# myg102.net
KiCad netlist of a schematic drawn in EasyEDA Pro
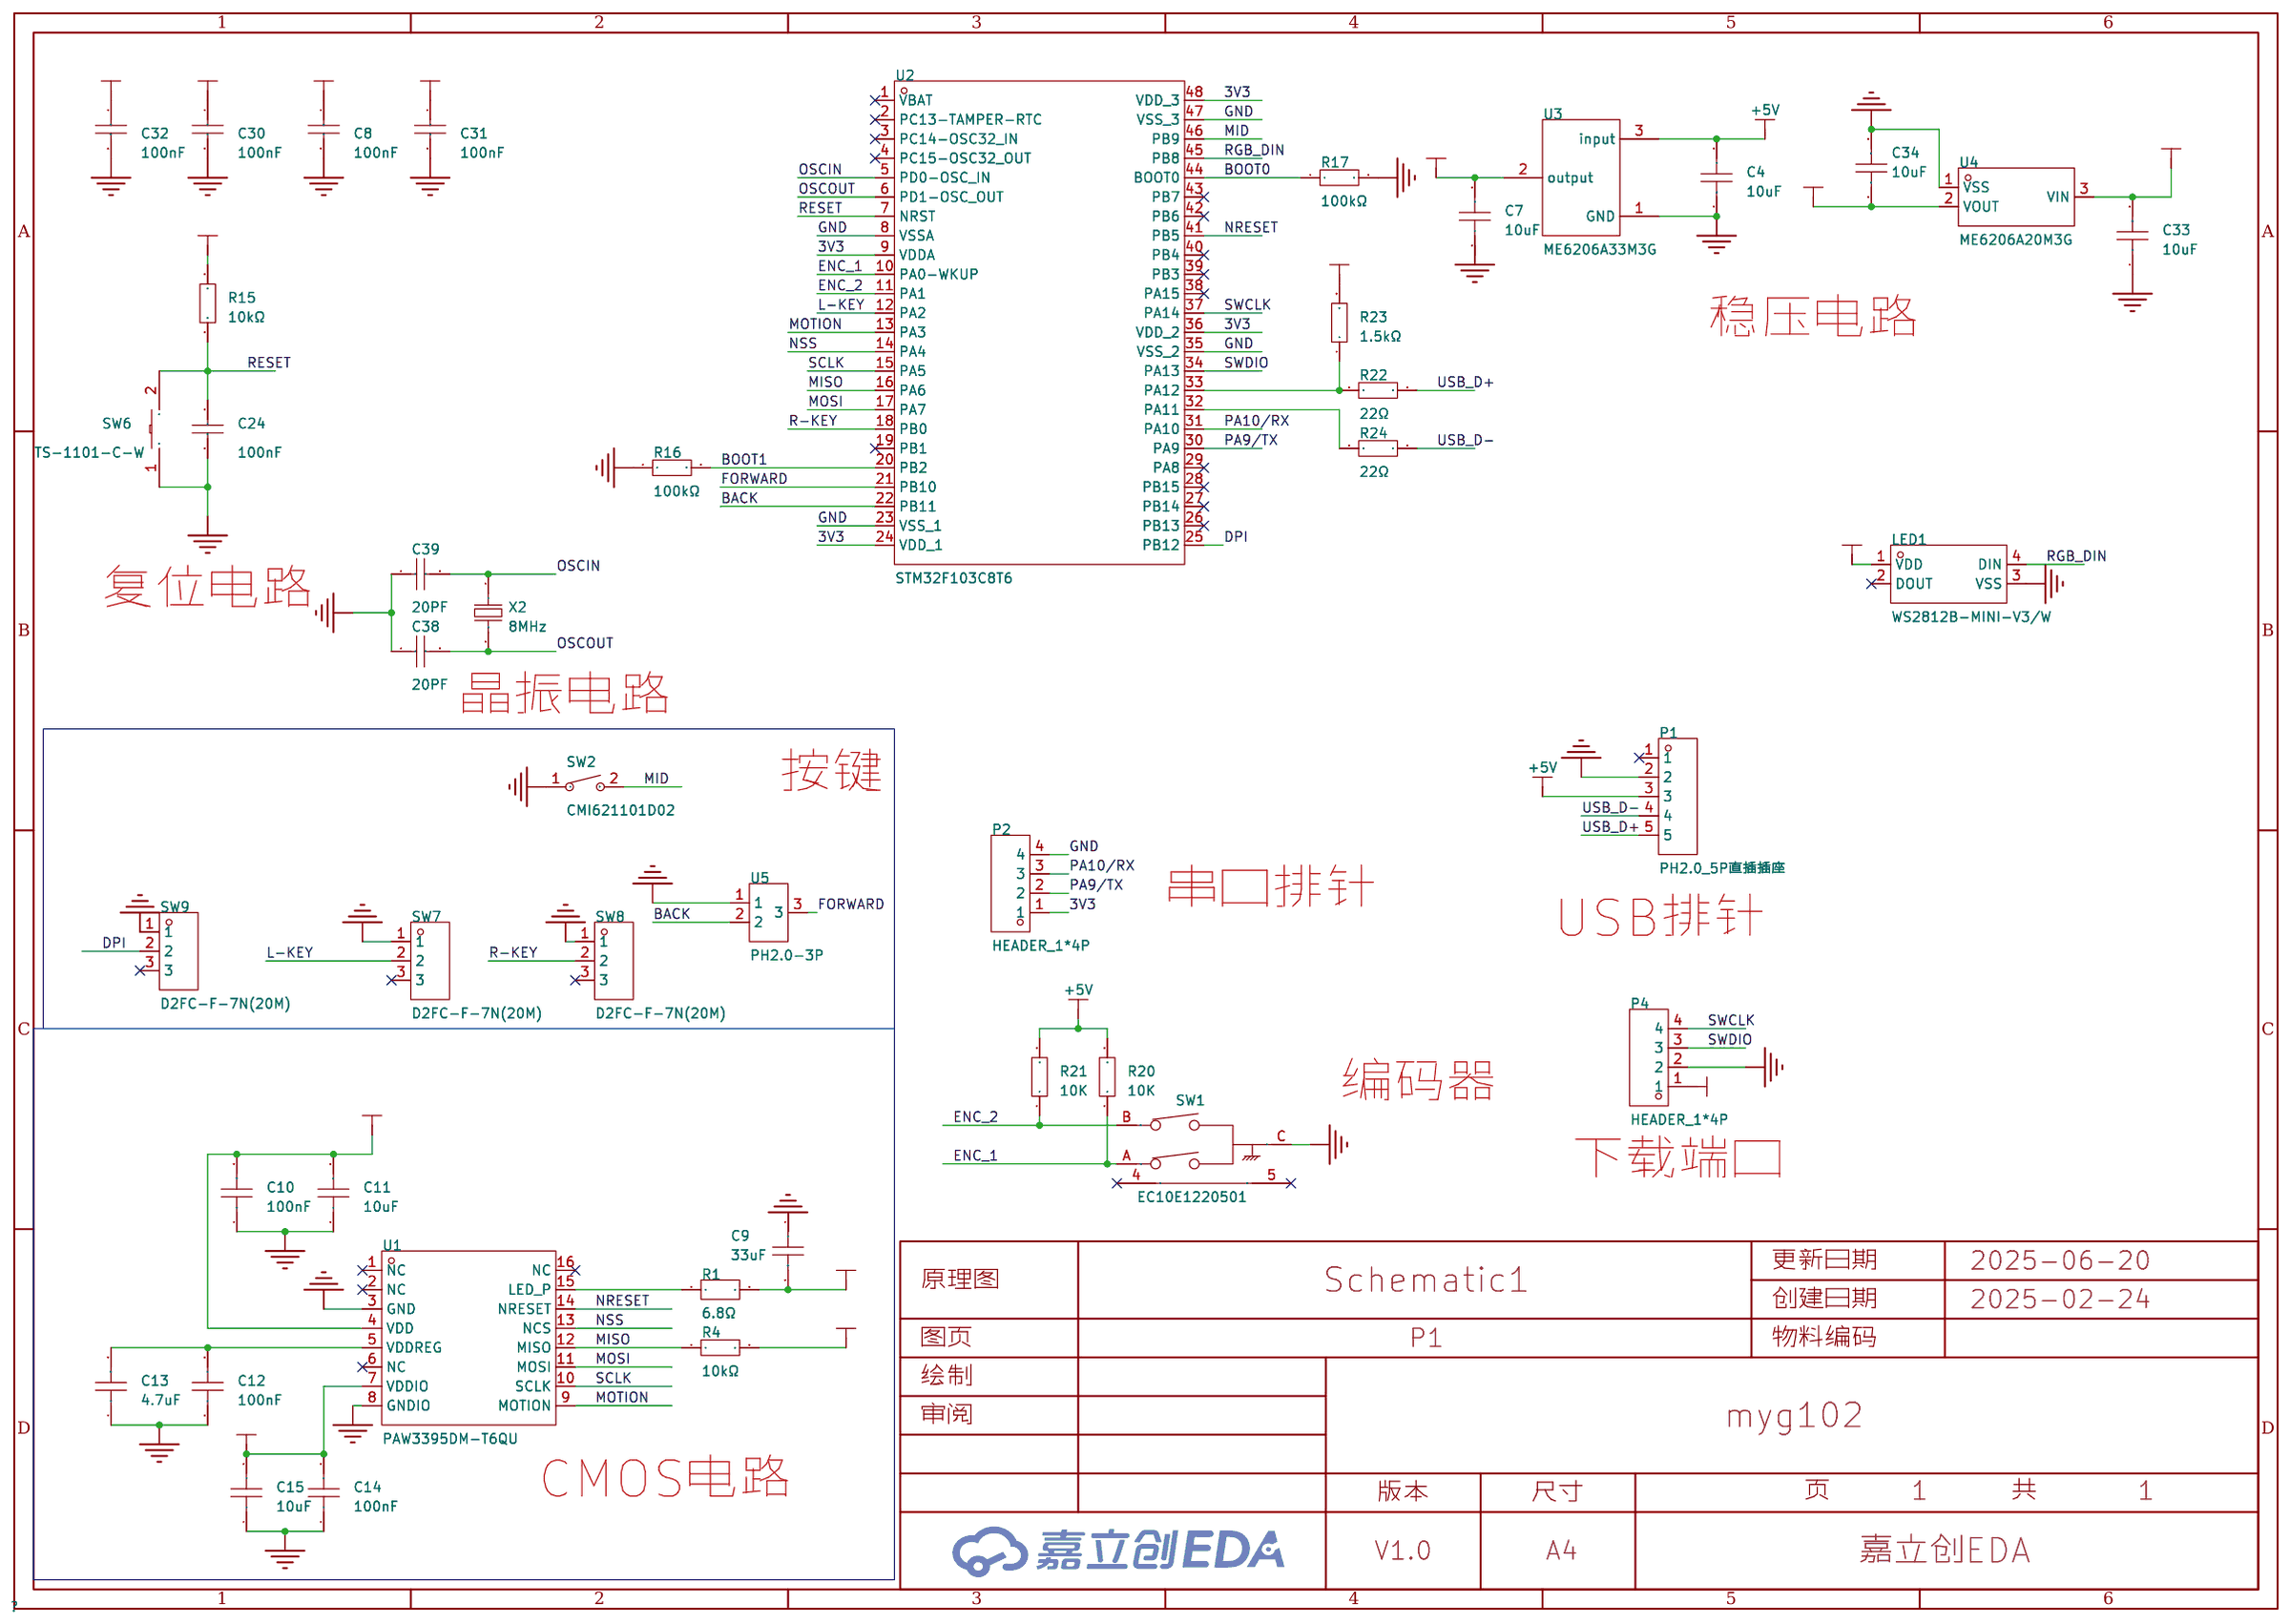
[diagram p0: schematic sheet]

(export (version "E")
  (design (tool "Eeschema 10.0.6"))
  (components
    (comp (ref "C4")
      (value "10uF")
      (footprint "easyedapro:C0603")
      (libsource (lib "easyedapro") (part "CapAcitance"))
    )
    (comp (ref "C7")
      (value "10uF")
      (footprint "easyedapro:C0603")
      (libsource (lib "easyedapro") (part "CapAcitance"))
    )
    (comp (ref "C8")
      (value "100nF")
      (footprint "easyedapro:C0603")
      (description "容值:100nF;精度:±10%;额定电压:50V;材质(温度系数):X7R;")
      (fields (field (name "Manufacturer Part") "0603B104K500NT") (field (name "Manufacturer") "FH(风华)"))
      (libsource (lib "easyedapro") (part "0603B104K500NT"))
    )
    (comp (ref "C9")
      (value "33uF")
      (footprint "easyedapro:C0603")
      (libsource (lib "easyedapro") (part "CapAcitance"))
    )
    (comp (ref "C10")
      (value "100nF")
      (footprint "easyedapro:C0603")
      (description "容值:100nF;精度:±10%;额定电压:50V;材质(温度系数):X7R;")
      (fields
        (field (name "Manufacturer Part") "CC0603KRX7R9BB104")
        (field (name "Manufacturer") "YAGEO(国巨)")
      )
      (libsource (lib "easyedapro") (part "CC0603KRX7R9BB104"))
    )
    (comp (ref "C11")
      (value "10uF")
      (footprint "easyedapro:C0603")
      (description "容值:10uF;精度:±20%;额定电压:25V;材质(温度系数):X5R;")
      (fields
        (field (name "Manufacturer Part") "CL10A106MA8NRNC")
        (field (name "Manufacturer") "SAMSUNG(三星)")
      )
      (libsource (lib "easyedapro") (part "CL10A106MA8NRNC"))
    )
    (comp (ref "C12")
      (value "100nF")
      (footprint "easyedapro:C0603")
      (description "容值:100nF;精度:±10%;额定电压:50V;材质(温度系数):X7R;")
      (fields
        (field (name "Manufacturer Part") "CC0603KRX7R9BB104")
        (field (name "Manufacturer") "YAGEO(国巨)")
      )
      (libsource (lib "easyedapro") (part "CC0603KRX7R9BB104"))
    )
    (comp (ref "C13")
      (value "4.7uF")
      (footprint "easyedapro:C0603")
      (description "容值:4.7uF;精度:±10%;额定电压:16V;材质(温度系数):X5R;")
      (fields
        (field (name "Manufacturer Part") "CL10A475KO8NNNC")
        (field (name "Manufacturer") "SAMSUNG(三星)")
      )
      (libsource (lib "easyedapro") (part "CL10A475KO8NNNC"))
    )
    (comp (ref "C14")
      (value "100nF")
      (footprint "easyedapro:C0603")
      (description "容值:100nF;精度:±10%;额定电压:50V;材质(温度系数):X7R;")
      (fields
        (field (name "Manufacturer Part") "CC0603KRX7R9BB104")
        (field (name "Manufacturer") "YAGEO(国巨)")
      )
      (libsource (lib "easyedapro") (part "CC0603KRX7R9BB104"))
    )
    (comp (ref "C15")
      (value "10uF")
      (footprint "easyedapro:C0603")
      (description "容值:10uF;精度:±20%;额定电压:25V;材质(温度系数):X5R;")
      (fields
        (field (name "Manufacturer Part") "CL10A106MA8NRNC")
        (field (name "Manufacturer") "SAMSUNG(三星)")
      )
      (libsource (lib "easyedapro") (part "CL10A106MA8NRNC"))
    )
    (comp (ref "C24")
      (value "100nF")
      (footprint "easyedapro:C0603")
      (description "容值:100nF;精度:±10%;额定电压:50V;材质(温度系数):X7R;")
      (fields (field (name "Manufacturer Part") "0603B104K500NT") (field (name "Manufacturer") "FH(风华)"))
      (libsource (lib "easyedapro") (part "0603B104K500NT"))
    )
    (comp (ref "C30")
      (value "100nF")
      (footprint "easyedapro:C0603")
      (description "容值:100nF;精度:±10%;额定电压:50V;材质(温度系数):X7R;")
      (fields (field (name "Manufacturer Part") "0603B104K500NT") (field (name "Manufacturer") "FH(风华)"))
      (libsource (lib "easyedapro") (part "0603B104K500NT"))
    )
    (comp (ref "C31")
      (value "100nF")
      (footprint "easyedapro:C0603")
      (description "容值:100nF;精度:±10%;额定电压:50V;材质(温度系数):X7R;")
      (fields (field (name "Manufacturer Part") "0603B104K500NT") (field (name "Manufacturer") "FH(风华)"))
      (libsource (lib "easyedapro") (part "0603B104K500NT"))
    )
    (comp (ref "C32")
      (value "100nF")
      (footprint "easyedapro:C0603")
      (description "容值:100nF;精度:±10%;额定电压:50V;材质(温度系数):X7R;")
      (fields (field (name "Manufacturer Part") "0603B104K500NT") (field (name "Manufacturer") "FH(风华)"))
      (libsource (lib "easyedapro") (part "0603B104K500NT"))
    )
    (comp (ref "C33")
      (value "10uF")
      (footprint "easyedapro:C0603")
      (libsource (lib "easyedapro") (part "CapAcitance"))
    )
    (comp (ref "C34")
      (value "10uF")
      (footprint "easyedapro:C0603")
      (libsource (lib "easyedapro") (part "CapAcitance"))
    )
    (comp (ref "C38")
      (value "20PF")
      (footprint "easyedapro:C0603")
      (description "容值:100nF;精度:±10%;额定电压:50V;材质(温度系数):X7R;")
      (fields (field (name "Manufacturer Part") "0603B104K500NT") (field (name "Manufacturer") "FH(风华)"))
      (libsource (lib "easyedapro") (part "0603B104K500NT"))
    )
    (comp (ref "C39")
      (value "20PF")
      (footprint "easyedapro:C0603")
      (description "容值:100nF;精度:±10%;额定电压:50V;材质(温度系数):X7R;")
      (fields (field (name "Manufacturer Part") "0603B104K500NT") (field (name "Manufacturer") "FH(风华)"))
      (libsource (lib "easyedapro") (part "0603B104K500NT"))
    )
    (comp (ref "LED1")
      (value "WS2812B-MINI-V3/W")
      (footprint "easyedapro:LED-SMD_4P-L3.5-W3.5-TL_WS2812B")
      (description "小尺寸3535，无需外围元器件，有反接保护和过压保护")
      (fields (field (name "Manufacturer") "worldsemi"))
      (libsource (lib "easyedapro") (part "WS2812B-MINI"))
    )
    (comp (ref "P1")
      (value "PH2.0_5P直插插座")
      (footprint "easyedapro:CONN-TH_5P-P2.00-PH5A")
      (libsource (lib "easyedapro") (part "PH2.0_5P直插插座"))
    )
    (comp (ref "P2")
      (value "HEADER_1*4P")
      (footprint "easyedapro:HDR-TH_4P-P2.54-V-M-1")
      (libsource (lib "easyedapro") (part "HEADER_1*4P"))
    )
    (comp (ref "P4")
      (value "HEADER_1*4P")
      (footprint "easyedapro:HDR-TH_4P-P2.54-V-M-1")
      (libsource (lib "easyedapro") (part "HEADER_1*4P"))
    )
    (comp (ref "R1")
      (value "6.8Ω")
      (footprint "easyedapro:R0603")
      (description "电阻类型:厚膜电阻;阻值:5.6Ω;精度:±1%;功率:100mW;最大工作电压:75V;温度系数:±200ppm/°C;")
      (fields (field (name "Manufacturer Part") "FRC0603F5R60TS") (field (name "Manufacturer") "FOJAN(富捷)"))
      (libsource (lib "easyedapro") (part "FRC0603F5R60TS"))
    )
    (comp (ref "R4")
      (value "10kΩ")
      (footprint "easyedapro:R0603")
      (description "电阻类型:厚膜电阻;阻值:10kΩ;精度:±1%;功率:100mW;最大工作电压:75V;温度系数:±100ppm/°C;")
      (fields
        (field (name "Manufacturer Part") "0603WAF1002T5E")
        (field (name "Manufacturer") "UNI-ROYAL(厚声)")
      )
      (libsource (lib "easyedapro") (part "0603WAF1002T5E"))
    )
    (comp (ref "R15")
      (value "10kΩ")
      (fields
        (field (name "Manufacturer Part") "0603WAF1002T5E")
        (field (name "Manufacturer") "UNI-ROYAL(厚声)")
      )
      (libsource (lib "easyedapro") (part "0603WAF1002T5E"))
    )
    (comp (ref "R16")
      (value "100kΩ")
      (footprint "easyedapro:R0603")
      (description "电阻类型:厚膜电阻;阻值:100kΩ;精度:±1%;功率:100mW;最大工作电压:75V;温度系数:±100ppm/°C;")
      (fields
        (field (name "Manufacturer Part") "0603WAF1003T5E")
        (field (name "Manufacturer") "UNI-ROYAL(厚声)")
      )
      (libsource (lib "easyedapro") (part "0603WAF1003T5E"))
    )
    (comp (ref "R17")
      (value "100kΩ")
      (footprint "easyedapro:R0603")
      (description "电阻类型:厚膜电阻;阻值:100kΩ;精度:±1%;功率:100mW;最大工作电压:75V;温度系数:±100ppm/°C;")
      (fields
        (field (name "Manufacturer Part") "0603WAF1003T5E")
        (field (name "Manufacturer") "UNI-ROYAL(厚声)")
      )
      (libsource (lib "easyedapro") (part "0603WAF1003T5E"))
    )
    (comp (ref "R20") (value "10K") (libsource (lib "easyedapro") (part "电阻")))
    (comp (ref "R21") (value "10K") (libsource (lib "easyedapro") (part "电阻")))
    (comp (ref "R22")
      (value "22Ω")
      (footprint "easyedapro:R0603")
      (description "电阻类型:厚膜电阻;阻值:1kΩ;精度:±1%;功率:100mW;最大工作电压:75V;温度系数:±100ppm/°C;")
      (fields
        (field (name "Manufacturer Part") "0603WAF1001T5E")
        (field (name "Manufacturer") "UNI-ROYAL(厚声)")
      )
      (libsource (lib "easyedapro") (part "0603WAF1001T5E"))
    )
    (comp (ref "R23")
      (value "1.5kΩ")
      (footprint "easyedapro:R0603")
      (description "电阻类型:厚膜电阻;阻值:100kΩ;精度:±1%;功率:100mW;最大工作电压:75V;温度系数:±100ppm/°C;")
      (fields
        (field (name "Manufacturer Part") "0603WAF1003T5E")
        (field (name "Manufacturer") "UNI-ROYAL(厚声)")
      )
      (libsource (lib "easyedapro") (part "0603WAF1003T5E"))
    )
    (comp (ref "R24")
      (value "22Ω")
      (footprint "easyedapro:R0603")
      (description "电阻类型:厚膜电阻;阻值:1kΩ;精度:±1%;功率:100mW;最大工作电压:75V;温度系数:±100ppm/°C;")
      (fields
        (field (name "Manufacturer Part") "0603WAF1001T5E")
        (field (name "Manufacturer") "UNI-ROYAL(厚声)")
      )
      (libsource (lib "easyedapro") (part "0603WAF1001T5E"))
    )
    (comp (ref "SW1")
      (value "EC10E1220501")
      (footprint "easyedapro:SW-TH_EC10EXXXXXXX")
      (description "10型贯通轴型")
      (fields (field (name "Manufacturer") "ALPSALPINE(阿尔卑斯阿尔派)"))
      (libsource (lib "easyedapro") (part "EC10E1220501"))
    )
    (comp (ref "SW2")
      (value "CMI621101D02")
      (footprint "easyedapro:SW-TH_L6.2-W6.2-P5.00")
      (fields (field (name "Manufacturer") "Kailh(凯华)"))
      (libsource (lib "easyedapro") (part "CMI621101D02"))
    )
    (comp (ref "SW6")
      (value "TS-1101-C-W")
      (footprint "easyedapro:SW-SMD_L6.0-W3.3-LS8.0")
      (description "触点电流:50mA;额定电压(AC):-;额定电压(DC):12V;额定功率:-;绝缘电阻:-;电路结构:单刀单掷;安装方式:立贴;带灯:无;作用力:260gf;机械寿命:5万次;带支架:否;")
      (fields (field (name "Manufacturer") "XKB Connectivity(中国星坤)"))
      (libsource (lib "easyedapro") (part "TS-1101-C-W"))
    )
    (comp (ref "SW7")
      (value "D2FC-F-7N(20M)")
      (footprint "easyedapro:SW-TH_3P-L12.8-W5.8-P5.08_DM3CQF1004L04")
      (fields (field (name "Manufacturer") "OMRON(欧姆龙)"))
      (libsource (lib "easyedapro") (part "D2FC-F-7N(20M)"))
    )
    (comp (ref "SW8")
      (value "D2FC-F-7N(20M)")
      (footprint "easyedapro:SW-TH_3P-L12.8-W5.8-P5.08_DM3CQF1004L04")
      (fields (field (name "Manufacturer") "OMRON(欧姆龙)"))
      (libsource (lib "easyedapro") (part "D2FC-F-7N(20M)"))
    )
    (comp (ref "SW9")
      (value "D2FC-F-7N(20M)")
      (footprint "easyedapro:SW-TH_3P-L12.8-W5.8-P5.08_DM3CQF1004L04")
      (fields (field (name "Manufacturer") "OMRON(欧姆龙)"))
      (libsource (lib "easyedapro") (part "D2FC-F-7N(20M)"))
    )
    (comp (ref "U1")
      (value "PAW3395DM-T6QU")
      (footprint "easyedapro:DIP-16_PAW3395DM-T6QU")
      (libsource (lib "easyedapro") (part "PAW3395DM-T6QU"))
    )
    (comp (ref "U2")
      (value "STM32F103C8T6")
      (footprint "easyedapro:LQFP-48_L7.0-W7.0-P0.50-LS9.0-BL")
      (description "CPU内核:ARM-M3;CPU最大主频:72MHz;应用领域:-;")
      (fields (field (name "Manufacturer") "ST(意法半导体)"))
      (libsource (lib "easyedapro") (part "STM32F103C8T6"))
    )
    (comp (ref "U3")
      (value "ME6206A33M3G")
      (footprint "easyedapro:SOT-23-3_L2.9-W1.6-P1.90-LS2.8-BR")
      (description "输出类型:固定;最大输入电压:6V;输出电压:3.3V;最大输出电流:300mA;电源纹波抑制比(PSRR):50dB@(1kHz);输出极性:正极;")
      (fields (field (name "Manufacturer") "MICRONE(南京微盟)"))
      (libsource (lib "easyedapro") (part "ME6206A33M3G"))
    )
    (comp (ref "U4")
      (value "ME6206A20M3G")
      (footprint "easyedapro:SOT-23-3_L3.0-W1.7-P0.95-LS2.9-BR")
      (description "输出类型:固定;最大输入电压:6V;输出电压:2V;最大输出电流:-;电源纹波抑制比(PSRR):45dB@(1kHz);输出极性:正极;")
      (fields (field (name "Manufacturer") "MICRONE(南京微盟)"))
      (libsource (lib "easyedapro") (part "ME6206A20M3G"))
    )
    (comp (ref "U5")
      (value "PH2.0-3P")
      (footprint "easyedapro:CONN-TH_3P-P2.00_HX20007-3A")
      (libsource (lib "easyedapro") (part "PH2.0-3P_C9900011646"))
    )
    (comp (ref "X2")
      (value "8MHz")
      (footprint "easyedapro:CRYSTAL-SMD_2P-L5.0-W3.2")
      (description "晶振类型:贴片晶振;频率:8MHz;常温频差:±10ppm;负载电容:20pF;频率稳定度(全温):±20ppm;")
      (fields (field (name "Manufacturer Part") "XG1SI-111-8M") (field (name "Manufacturer") "YXC(扬兴晶振)"))
      (libsource (lib "easyedapro") (part "XG1SI-111-8M"))
    )
  )
  (nets
    (net (code "1") (name "+5V") (class "Default")
      (node (ref "C4") (pin "2") (pinfunction "2_2") (pintype "input"))
      (node (ref "LED1") (pin "1") (pinfunction "VDD_1") (pintype "unspecified"))
      (node (ref "P1") (pin "3") (pinfunction "3_3") (pintype "unspecified"))
      (node (ref "R20") (pin "2") (pinfunction "2_2") (pintype "input"))
      (node (ref "R21") (pin "2") (pinfunction "2_2") (pintype "input"))
      (node (ref "U3") (pin "3") (pinfunction "input_3") (pintype "unspecified"))
    )
    (net (code "2") (name "/BACK") (class "Default")
      (node (ref "U2") (pin "22") (pinfunction "PB11_22") (pintype "unspecified"))
      (node (ref "U5") (pin "2") (pinfunction "2_2") (pintype "unspecified"))
    )
    (net (code "3") (name "/BOOT0") (class "Default")
      (node (ref "R17") (pin "1") (pinfunction "1_1") (pintype "input"))
      (node (ref "U2") (pin "44") (pinfunction "BOOT0_44") (pintype "unspecified"))
    )
    (net (code "4") (name "/BOOT1") (class "Default")
      (node (ref "R16") (pin "2") (pinfunction "2_2") (pintype "input"))
      (node (ref "U2") (pin "20") (pinfunction "PB2_20") (pintype "unspecified"))
    )
    (net (code "5") (name "/DPI") (class "Default")
      (node (ref "SW9") (pin "2") (pinfunction "2_2") (pintype "unspecified"))
      (node (ref "U2") (pin "25") (pinfunction "PB12_25") (pintype "unspecified"))
    )
    (net (code "6") (name "/ENC_1") (class "Default")
      (node (ref "R20") (pin "1") (pinfunction "1_1") (pintype "input"))
      (node (ref "SW1") (pin "A") (pinfunction "A_A") (pintype "input"))
      (node (ref "U2") (pin "10") (pinfunction "PA0-WKUP_10") (pintype "unspecified"))
    )
    (net (code "7") (name "/ENC_2") (class "Default")
      (node (ref "R21") (pin "1") (pinfunction "1_1") (pintype "input"))
      (node (ref "SW1") (pin "B") (pinfunction "B_B") (pintype "input"))
      (node (ref "U2") (pin "11") (pinfunction "PA1_11") (pintype "unspecified"))
    )
    (net (code "8") (name "/FORWARD") (class "Default")
      (node (ref "U2") (pin "21") (pinfunction "PB10_21") (pintype "unspecified"))
      (node (ref "U5") (pin "3") (pinfunction "3_3") (pintype "unspecified"))
    )
    (net (code "9") (name "/L-KEY") (class "Default")
      (node (ref "SW7") (pin "2") (pinfunction "2_2") (pintype "unspecified"))
      (node (ref "U2") (pin "12") (pinfunction "PA2_12") (pintype "unspecified"))
    )
    (net (code "10") (name "/MID") (class "Default")
      (node (ref "SW2") (pin "2") (pinfunction "2_2") (pintype "unspecified"))
      (node (ref "U2") (pin "46") (pinfunction "PB9_46") (pintype "unspecified"))
    )
    (net (code "11") (name "/MISO") (class "Default")
      (node (ref "R4") (pin "1") (pinfunction "1_1") (pintype "input"))
      (node (ref "U1") (pin "12") (pinfunction "MISO_12") (pintype "input"))
      (node (ref "U2") (pin "16") (pinfunction "PA6_16") (pintype "unspecified"))
    )
    (net (code "12") (name "/MOSI") (class "Default")
      (node (ref "U1") (pin "11") (pinfunction "MOSI_11") (pintype "input"))
      (node (ref "U2") (pin "17") (pinfunction "PA7_17") (pintype "unspecified"))
    )
    (net (code "13") (name "/MOTION") (class "Default")
      (node (ref "U1") (pin "9") (pinfunction "MOTION_9") (pintype "input"))
      (node (ref "U2") (pin "13") (pinfunction "PA3_13") (pintype "unspecified"))
    )
    (net (code "14") (name "/NRESET") (class "Default")
      (node (ref "U1") (pin "14") (pinfunction "NRESET_14") (pintype "input"))
      (node (ref "U2") (pin "41") (pinfunction "PB5_41") (pintype "unspecified"))
    )
    (net (code "15") (name "/NSS") (class "Default")
      (node (ref "U1") (pin "13") (pinfunction "NCS_13") (pintype "input"))
      (node (ref "U2") (pin "14") (pinfunction "PA4_14") (pintype "unspecified"))
    )
    (net (code "16") (name "/OSCIN") (class "Default")
      (node (ref "C39") (pin "2") (pinfunction "2_2") (pintype "input"))
      (node (ref "U2") (pin "5") (pinfunction "PD0-OSC_IN_5") (pintype "unspecified"))
      (node (ref "X2") (pin "1") (pinfunction "1_1") (pintype "unspecified"))
    )
    (net (code "17") (name "/OSCOUT") (class "Default")
      (node (ref "C38") (pin "2") (pinfunction "2_2") (pintype "input"))
      (node (ref "U2") (pin "6") (pinfunction "PD1-OSC_OUT_6") (pintype "unspecified"))
      (node (ref "X2") (pin "2") (pinfunction "2_2") (pintype "unspecified"))
    )
    (net (code "18") (name "/PA9{slash}TX") (class "Default")
      (node (ref "P2") (pin "2") (pinfunction "2_2") (pintype "input"))
      (node (ref "U2") (pin "30") (pinfunction "PA9_30") (pintype "unspecified"))
    )
    (net (code "19") (name "/PA10{slash}RX") (class "Default")
      (node (ref "P2") (pin "3") (pinfunction "3_3") (pintype "input"))
      (node (ref "U2") (pin "31") (pinfunction "PA10_31") (pintype "unspecified"))
    )
    (net (code "20") (name "/R-KEY") (class "Default")
      (node (ref "SW8") (pin "2") (pinfunction "2_2") (pintype "unspecified"))
      (node (ref "U2") (pin "18") (pinfunction "PB0_18") (pintype "unspecified"))
    )
    (net (code "21") (name "/RESET") (class "Default")
      (node (ref "C24") (pin "2") (pinfunction "2_2") (pintype "input"))
      (node (ref "R15") (pin "1") (pinfunction "1_1") (pintype "input"))
      (node (ref "SW6") (pin "2") (pinfunction "2_2") (pintype "input"))
      (node (ref "U2") (pin "7") (pinfunction "NRST_7") (pintype "unspecified"))
    )
    (net (code "22") (name "/RGB_DIN") (class "Default")
      (node (ref "LED1") (pin "4") (pinfunction "DIN_4") (pintype "unspecified"))
      (node (ref "U2") (pin "45") (pinfunction "PB8_45") (pintype "unspecified"))
    )
    (net (code "23") (name "/SCLK") (class "Default")
      (node (ref "U1") (pin "10") (pinfunction "SCLK_10") (pintype "input"))
      (node (ref "U2") (pin "15") (pinfunction "PA5_15") (pintype "unspecified"))
    )
    (net (code "24") (name "/SWCLK") (class "Default")
      (node (ref "P4") (pin "4") (pinfunction "4_4") (pintype "input"))
      (node (ref "U2") (pin "37") (pinfunction "PA14_37") (pintype "unspecified"))
    )
    (net (code "25") (name "/SWDIO") (class "Default")
      (node (ref "P4") (pin "3") (pinfunction "3_3") (pintype "input"))
      (node (ref "U2") (pin "34") (pinfunction "PA13_34") (pintype "unspecified"))
    )
    (net (code "26") (name "/USB_D+") (class "Default")
      (node (ref "P1") (pin "5") (pinfunction "5_5") (pintype "unspecified"))
      (node (ref "R22") (pin "2") (pinfunction "2_2") (pintype "input"))
    )
    (net (code "27") (name "/USB_D-") (class "Default")
      (node (ref "P1") (pin "4") (pinfunction "4_4") (pintype "unspecified"))
      (node (ref "R24") (pin "2") (pinfunction "2_2") (pintype "input"))
    )
    (net (code "28") (name "2V") (class "Default")
      (node (ref "C10") (pin "2") (pinfunction "2_2") (pintype "unspecified"))
      (node (ref "C11") (pin "2") (pinfunction "2_2") (pintype "unspecified"))
      (node (ref "C34") (pin "1") (pinfunction "1_1") (pintype "input"))
      (node (ref "C9") (pin "2") (pinfunction "2_2") (pintype "input"))
      (node (ref "R1") (pin "2") (pinfunction "2_2") (pintype "unspecified"))
      (node (ref "U1") (pin "4") (pinfunction "VDD_4") (pintype "input"))
      (node (ref "U4") (pin "2") (pinfunction "VOUT_2") (pintype "unspecified"))
    )
    (net (code "29") (name "3V3") (class "Default")
      (node (ref "C14") (pin "2") (pinfunction "2_2") (pintype "unspecified"))
      (node (ref "C15") (pin "2") (pinfunction "2_2") (pintype "unspecified"))
      (node (ref "C30") (pin "1") (pinfunction "1_1") (pintype "input"))
      (node (ref "C31") (pin "1") (pinfunction "1_1") (pintype "input"))
      (node (ref "C32") (pin "1") (pinfunction "1_1") (pintype "input"))
      (node (ref "C33") (pin "2") (pinfunction "2_2") (pintype "input"))
      (node (ref "C7") (pin "2") (pinfunction "2_2") (pintype "input"))
      (node (ref "C8") (pin "1") (pinfunction "1_1") (pintype "input"))
      (node (ref "P2") (pin "1") (pinfunction "1_1") (pintype "input"))
      (node (ref "P4") (pin "1") (pinfunction "1_1") (pintype "input"))
      (node (ref "R15") (pin "2") (pinfunction "2_2") (pintype "input"))
      (node (ref "R23") (pin "2") (pinfunction "2_2") (pintype "input"))
      (node (ref "R4") (pin "2") (pinfunction "2_2") (pintype "input"))
      (node (ref "U1") (pin "7") (pinfunction "VDDIO_7") (pintype "input"))
      (node (ref "U2") (pin "24") (pinfunction "VDD_1_24") (pintype "unspecified"))
      (node (ref "U2") (pin "36") (pinfunction "VDD_2_36") (pintype "unspecified"))
      (node (ref "U2") (pin "48") (pinfunction "VDD_3_48") (pintype "unspecified"))
      (node (ref "U2") (pin "9") (pinfunction "VDDA_9") (pintype "unspecified"))
      (node (ref "U3") (pin "2") (pinfunction "output_2") (pintype "unspecified"))
      (node (ref "U4") (pin "3") (pinfunction "VIN_3") (pintype "unspecified"))
    )
    (net (code "30") (name "GND") (class "Default")
      (node (ref "C10") (pin "1") (pinfunction "1_1") (pintype "unspecified"))
      (node (ref "C11") (pin "1") (pinfunction "1_1") (pintype "unspecified"))
      (node (ref "C12") (pin "1") (pinfunction "1_1") (pintype "unspecified"))
      (node (ref "C13") (pin "1") (pinfunction "1_1") (pintype "unspecified"))
      (node (ref "C14") (pin "1") (pinfunction "1_1") (pintype "unspecified"))
      (node (ref "C15") (pin "1") (pinfunction "1_1") (pintype "unspecified"))
      (node (ref "C24") (pin "1") (pinfunction "1_1") (pintype "input"))
      (node (ref "C30") (pin "2") (pinfunction "2_2") (pintype "input"))
      (node (ref "C31") (pin "2") (pinfunction "2_2") (pintype "input"))
      (node (ref "C32") (pin "2") (pinfunction "2_2") (pintype "input"))
      (node (ref "C33") (pin "1") (pinfunction "1_1") (pintype "input"))
      (node (ref "C34") (pin "2") (pinfunction "2_2") (pintype "input"))
      (node (ref "C38") (pin "1") (pinfunction "1_1") (pintype "input"))
      (node (ref "C39") (pin "1") (pinfunction "1_1") (pintype "input"))
      (node (ref "C4") (pin "1") (pinfunction "1_1") (pintype "input"))
      (node (ref "C7") (pin "1") (pinfunction "1_1") (pintype "input"))
      (node (ref "C8") (pin "2") (pinfunction "2_2") (pintype "input"))
      (node (ref "C9") (pin "1") (pinfunction "1_1") (pintype "input"))
      (node (ref "LED1") (pin "3") (pinfunction "VSS_3") (pintype "unspecified"))
      (node (ref "P1") (pin "2") (pinfunction "2_2") (pintype "unspecified"))
      (node (ref "P2") (pin "4") (pinfunction "4_4") (pintype "input"))
      (node (ref "P4") (pin "2") (pinfunction "2_2") (pintype "input"))
      (node (ref "R16") (pin "1") (pinfunction "1_1") (pintype "input"))
      (node (ref "R17") (pin "2") (pinfunction "2_2") (pintype "input"))
      (node (ref "SW1") (pin "C") (pinfunction "C_C") (pintype "input"))
      (node (ref "SW2") (pin "1") (pinfunction "1_1") (pintype "unspecified"))
      (node (ref "SW6") (pin "1") (pinfunction "1_1") (pintype "input"))
      (node (ref "SW7") (pin "1") (pinfunction "1_1") (pintype "unspecified"))
      (node (ref "SW8") (pin "1") (pinfunction "1_1") (pintype "unspecified"))
      (node (ref "SW9") (pin "1") (pinfunction "1_1") (pintype "unspecified"))
      (node (ref "U1") (pin "3") (pinfunction "GND_3") (pintype "input"))
      (node (ref "U1") (pin "8") (pinfunction "GNDIO_8") (pintype "input"))
      (node (ref "U2") (pin "23") (pinfunction "VSS_1_23") (pintype "unspecified"))
      (node (ref "U2") (pin "35") (pinfunction "VSS_2_35") (pintype "unspecified"))
      (node (ref "U2") (pin "47") (pinfunction "VSS_3_47") (pintype "unspecified"))
      (node (ref "U2") (pin "8") (pinfunction "VSSA_8") (pintype "unspecified"))
      (node (ref "U3") (pin "1") (pinfunction "GND_1") (pintype "unspecified"))
      (node (ref "U4") (pin "1") (pinfunction "VSS_1") (pintype "unspecified"))
      (node (ref "U5") (pin "1") (pinfunction "1_1") (pintype "unspecified"))
    )
    (net (code "31") (name "Net-(U1-LED_P)") (class "Default")
      (node (ref "R1") (pin "1") (pinfunction "1_1") (pintype "unspecified"))
      (node (ref "U1") (pin "15") (pinfunction "LED_P_15") (pintype "input"))
    )
    (net (code "32") (name "Net-(U1-VDDREG)") (class "Default")
      (node (ref "C12") (pin "2") (pinfunction "2_2") (pintype "unspecified"))
      (node (ref "C13") (pin "2") (pinfunction "2_2") (pintype "unspecified"))
      (node (ref "U1") (pin "5") (pinfunction "VDDREG_5") (pintype "input"))
    )
    (net (code "33") (name "Net-(U2-PA11)") (class "Default")
      (node (ref "R24") (pin "1") (pinfunction "1_1") (pintype "input"))
      (node (ref "U2") (pin "32") (pinfunction "PA11_32") (pintype "unspecified"))
    )
    (net (code "34") (name "Net-(U2-PA12)") (class "Default")
      (node (ref "R22") (pin "1") (pinfunction "1_1") (pintype "input"))
      (node (ref "R23") (pin "1") (pinfunction "1_1") (pintype "input"))
      (node (ref "U2") (pin "33") (pinfunction "PA12_33") (pintype "unspecified"))
    )
    (net (code "35") (name "unconnected-(LED1-DOUT-Pad2)") (class "Default")
      (node (ref "LED1") (pin "2") (pinfunction "DOUT_2") (pintype "unspecified+no_connect"))
    )
    (net (code "36") (name "unconnected-(P1-Pad1)") (class "Default")
      (node (ref "P1") (pin "1") (pinfunction "1_1") (pintype "unspecified+no_connect"))
    )
    (net (code "37") (name "unconnected-(SW1-Pad4)") (class "Default")
      (node (ref "SW1") (pin "4") (pinfunction "4_4") (pintype "input+no_connect"))
    )
    (net (code "38") (name "unconnected-(SW1-Pad5)") (class "Default")
      (node (ref "SW1") (pin "5") (pinfunction "5_5") (pintype "input+no_connect"))
    )
    (net (code "39") (name "unconnected-(SW7-Pad3)") (class "Default")
      (node (ref "SW7") (pin "3") (pinfunction "3_3") (pintype "unspecified+no_connect"))
    )
    (net (code "40") (name "unconnected-(SW8-Pad3)") (class "Default")
      (node (ref "SW8") (pin "3") (pinfunction "3_3") (pintype "unspecified+no_connect"))
    )
    (net (code "41") (name "unconnected-(SW9-Pad3)") (class "Default")
      (node (ref "SW9") (pin "3") (pinfunction "3_3") (pintype "unspecified+no_connect"))
    )
    (net (code "42") (name "unconnected-(U1-NC-Pad1)") (class "Default")
      (node (ref "U1") (pin "1") (pinfunction "NC_1") (pintype "input+no_connect"))
    )
    (net (code "43") (name "unconnected-(U1-NC-Pad2)") (class "Default")
      (node (ref "U1") (pin "2") (pinfunction "NC_2") (pintype "input+no_connect"))
    )
    (net (code "44") (name "unconnected-(U1-NC-Pad6)") (class "Default")
      (node (ref "U1") (pin "6") (pinfunction "NC_6") (pintype "input+no_connect"))
    )
    (net (code "45") (name "unconnected-(U1-NC-Pad16)") (class "Default")
      (node (ref "U1") (pin "16") (pinfunction "NC_16") (pintype "input+no_connect"))
    )
    (net (code "46") (name "unconnected-(U2-PA8-Pad29)") (class "Default")
      (node (ref "U2") (pin "29") (pinfunction "PA8_29") (pintype "unspecified+no_connect"))
    )
    (net (code "47") (name "unconnected-(U2-PA15-Pad38)") (class "Default")
      (node (ref "U2") (pin "38") (pinfunction "PA15_38") (pintype "unspecified+no_connect"))
    )
    (net (code "48") (name "unconnected-(U2-PB1-Pad19)") (class "Default")
      (node (ref "U2") (pin "19") (pinfunction "PB1_19") (pintype "unspecified+no_connect"))
    )
    (net (code "49") (name "unconnected-(U2-PB3-Pad39)") (class "Default")
      (node (ref "U2") (pin "39") (pinfunction "PB3_39") (pintype "unspecified+no_connect"))
    )
    (net (code "50") (name "unconnected-(U2-PB4-Pad40)") (class "Default")
      (node (ref "U2") (pin "40") (pinfunction "PB4_40") (pintype "unspecified+no_connect"))
    )
    (net (code "51") (name "unconnected-(U2-PB6-Pad42)") (class "Default")
      (node (ref "U2") (pin "42") (pinfunction "PB6_42") (pintype "unspecified+no_connect"))
    )
    (net (code "52") (name "unconnected-(U2-PB7-Pad43)") (class "Default")
      (node (ref "U2") (pin "43") (pinfunction "PB7_43") (pintype "unspecified+no_connect"))
    )
    (net (code "53") (name "unconnected-(U2-PB13-Pad26)") (class "Default")
      (node (ref "U2") (pin "26") (pinfunction "PB13_26") (pintype "unspecified+no_connect"))
    )
    (net (code "54") (name "unconnected-(U2-PB14-Pad27)") (class "Default")
      (node (ref "U2") (pin "27") (pinfunction "PB14_27") (pintype "unspecified+no_connect"))
    )
    (net (code "55") (name "unconnected-(U2-PB15-Pad28)") (class "Default")
      (node (ref "U2") (pin "28") (pinfunction "PB15_28") (pintype "unspecified+no_connect"))
    )
    (net (code "56") (name "unconnected-(U2-PC13-TAMPER-RTC-Pad2)") (class "Default")
      (node (ref "U2") (pin "2") (pinfunction "PC13-TAMPER-RTC_2") (pintype "unspecified+no_connect"))
    )
    (net (code "57") (name "unconnected-(U2-PC14-OSC32_IN-Pad3)") (class "Default")
      (node (ref "U2") (pin "3") (pinfunction "PC14-OSC32_IN_3") (pintype "unspecified+no_connect"))
    )
    (net (code "58") (name "unconnected-(U2-PC15-OSC32_OUT-Pad4)") (class "Default")
      (node (ref "U2") (pin "4") (pinfunction "PC15-OSC32_OUT_4") (pintype "unspecified+no_connect"))
    )
    (net (code "59") (name "unconnected-(U2-VBAT-Pad1)") (class "Default")
      (node (ref "U2") (pin "1") (pinfunction "VBAT_1") (pintype "unspecified+no_connect"))
    )
  )
)
